# Connector.net
KiCad netlist of a schematic drawn in Altium Designer
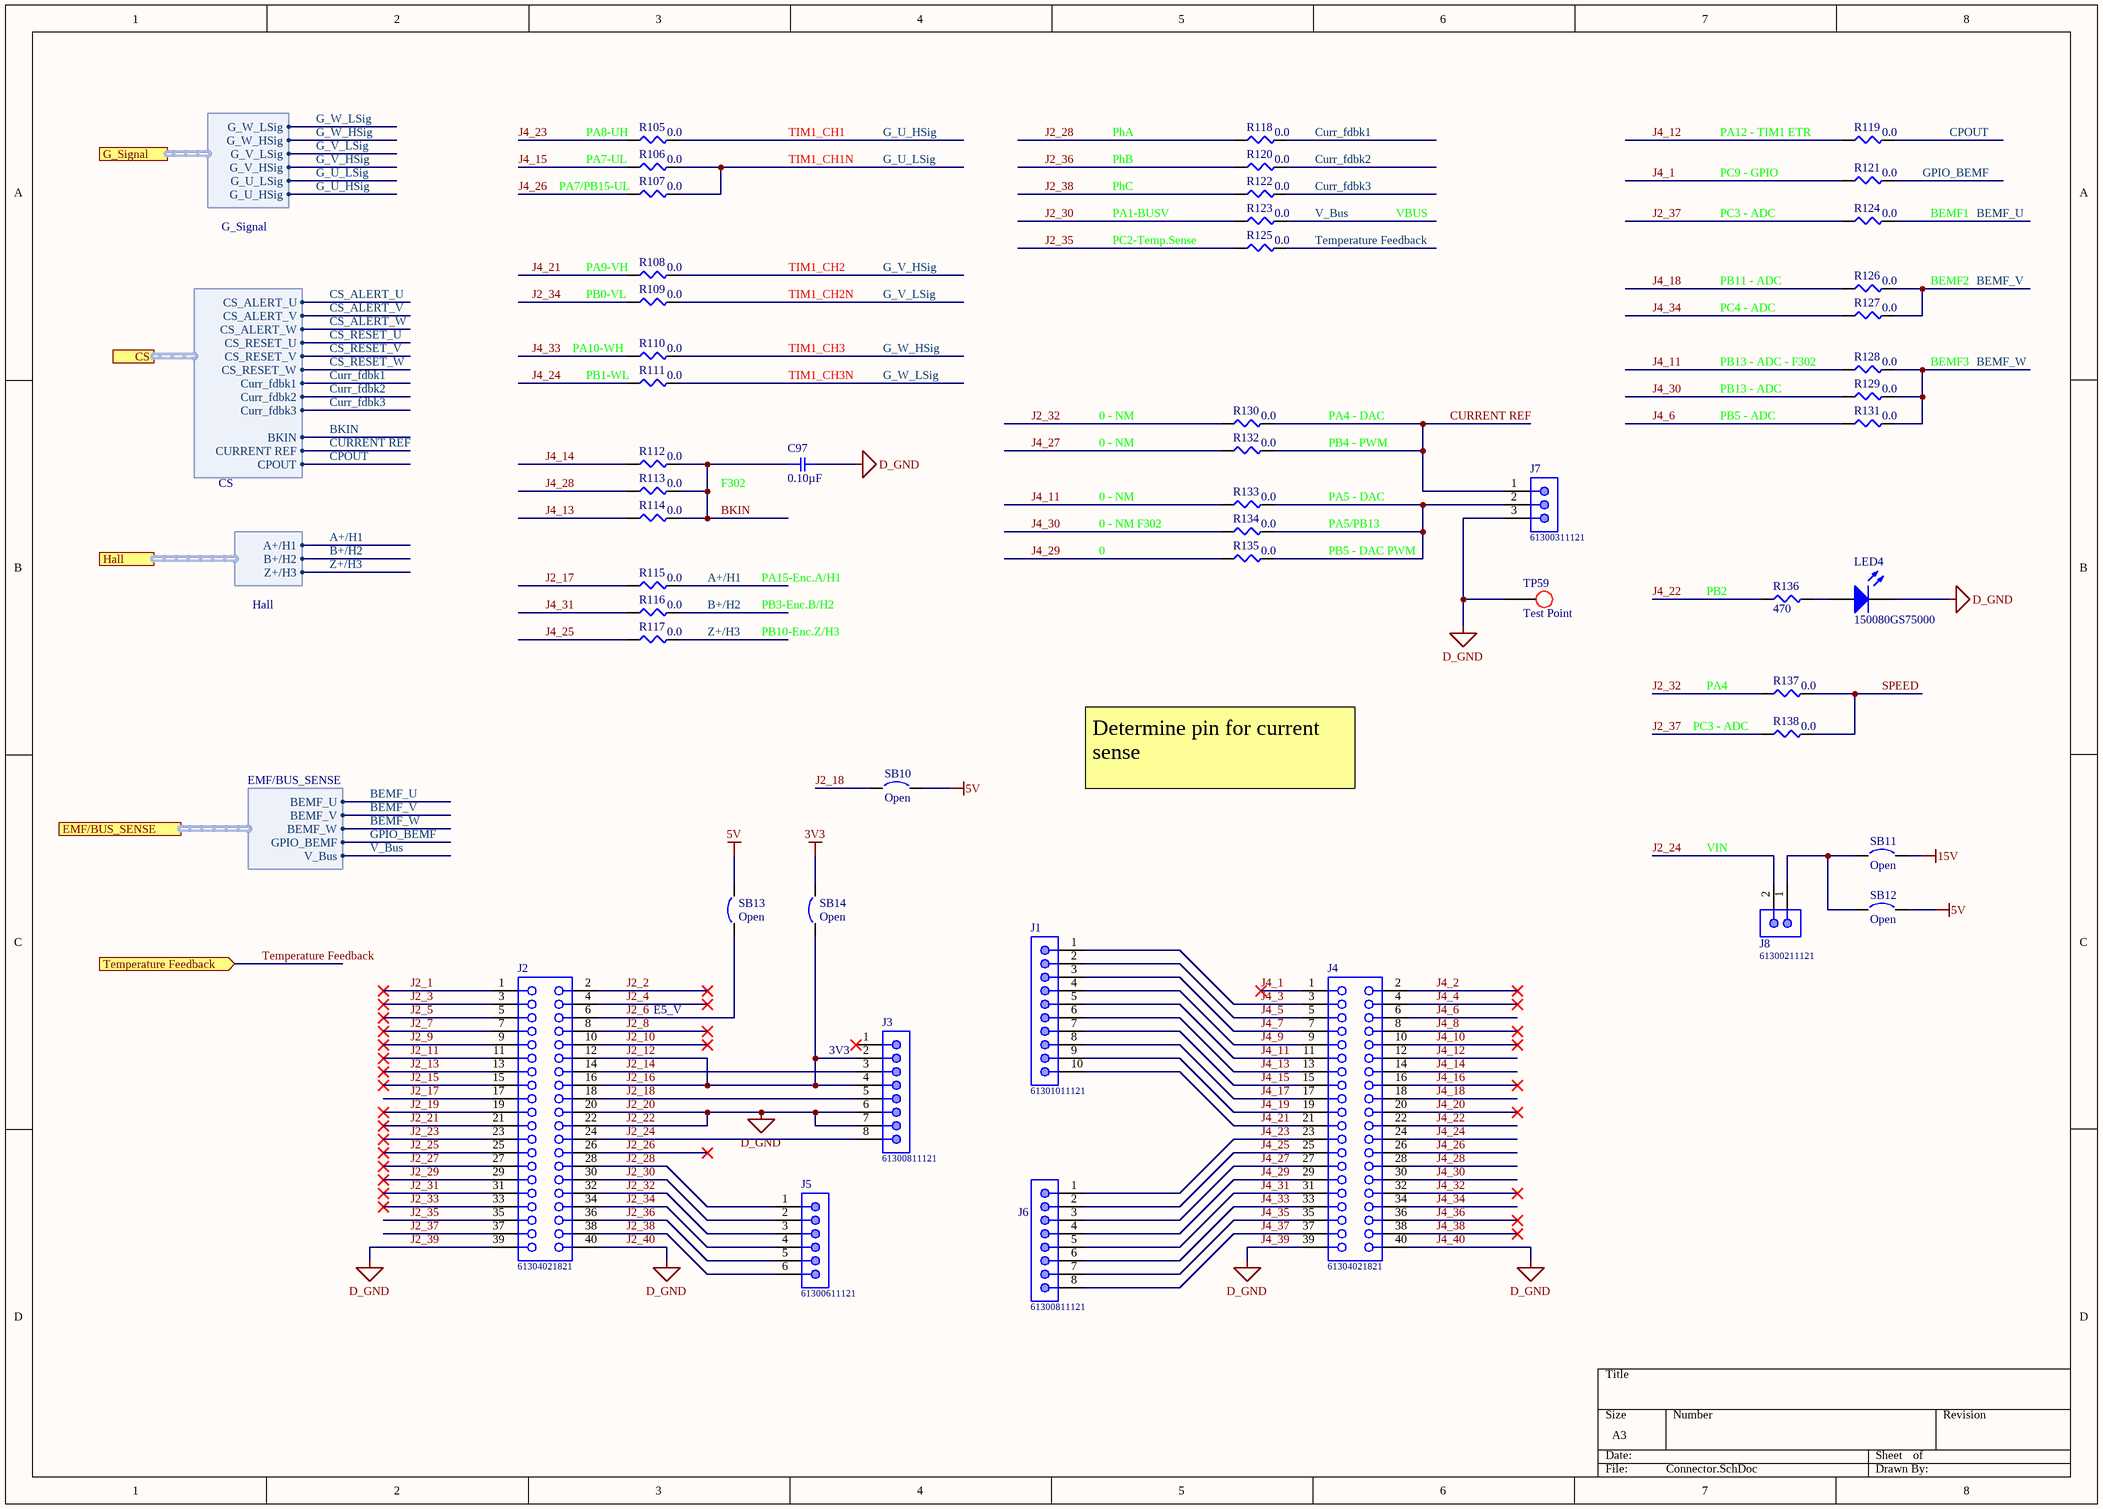
[diagram p0: Connector.SchDoc]

(export (version "E")
  (design (tool "Eeschema 10.0.6"))
  (components
    (comp (ref "C97")
      (value "0.10µF")
      (footprint "SMD-0805C")
      (description "CAP CER 0.1UF 50V X7R 0805")
      (fields
        (field (name "DIGI-KEY PART NUMBER") "490-11955-1-ND")
        (field (name "PART NUMBER") "GCD21BR71H104KA01L")
      )
      (libsource (lib "capacitor_murata_0805") (part "GCD21BR71H104KA01L"))
    )
    (comp (ref "J1")
      (value "61301011121")
      (footprint "61301011121")
      (description "WR-PHD Pin Header, THT, pitch 2.54mm, Single Row, Vertical, 10pin")
      (fields (field (name "PUBLISHER") "Wurth Elektronik"))
      (libsource (lib "o155175v243 Altium_WR-PHD (rev19a)") (part "61301011121"))
    )
    (comp (ref "J2")
      (value "61304021821")
      (footprint "61304021821")
      (description "WR-PHD Socket Header, THT, pitch 2.54mm, Dual Row, Vertical, 40pin")
      (fields (field (name "PUBLISHER") "Wurth Elektronik"))
      (libsource (lib "o155175v243 Altium_WR-PHD (rev19a)") (part "61304021821"))
    )
    (comp (ref "J3")
      (value "61300811121")
      (footprint "61300811121")
      (description "WR-PHD Pin Header, THT, pitch 2.54mm, Single Row, Vertical, 8pin")
      (fields (field (name "PUBLISHER") "Wurth Elektronik"))
      (libsource (lib "o155175v243 Altium_WR-PHD (rev19a)") (part "61300811121"))
    )
    (comp (ref "J4")
      (value "61304021821")
      (footprint "61304021821")
      (description "WR-PHD Socket Header, THT, pitch 2.54mm, Dual Row, Vertical, 40pin")
      (fields (field (name "PUBLISHER") "Wurth Elektronik"))
      (libsource (lib "o155175v243 Altium_WR-PHD (rev19a)") (part "61304021821"))
    )
    (comp (ref "J5")
      (value "61300611121")
      (footprint "61300611121")
      (description "WR-PHD Pin Header, THT, pitch 2.54mm, Single Row, Vertical, 6pin")
      (fields (field (name "PUBLISHER") "Wurth Elektronik"))
      (libsource (lib "o155175v243 Altium_WR-PHD (rev19a)") (part "61300611121"))
    )
    (comp (ref "J6")
      (value "61300811121")
      (footprint "61300811121")
      (description "WR-PHD Pin Header, THT, pitch 2.54mm, Single Row, Vertical, 8pin")
      (fields (field (name "PUBLISHER") "Wurth Elektronik"))
      (libsource (lib "o155175v243 Altium_WR-PHD (rev19a)") (part "61300811121"))
    )
    (comp (ref "J7")
      (value "61300311121")
      (footprint "61300311121")
      (description "WR-PHD Pin Header, THT, pitch 2.54mm, Single Row, Vertical, 3pin")
      (fields (field (name "PUBLISHER") "Wurth Elektronik"))
      (libsource (lib "o155175v243 Altium_WR-PHD (rev19a)") (part "61300311121"))
    )
    (comp (ref "J8")
      (value "61300211121")
      (footprint "61300211121")
      (description "WR-PHD Pin Header, THT, pitch 2.54mm, Single Row, Vertical, 2pin")
      (fields (field (name "PUBLISHER") "Wurth Elektronik"))
      (libsource (lib "o155175v243 Altium_WR-PHD (rev19a)") (part "61300211121"))
    )
    (comp (ref "LED4")
      (value "150080GS75000")
      (footprint "0805_A")
      (description "SMD mono-color Chip LED, WL-SMCW, Green")
      (libsource (lib "WL-SMCW SMD chip LED top view mono-color waterclear") (part "150080GS75000"))
    )
    (comp (ref "R105")
      (value "0.0")
      (footprint "SMD-0603-RES")
      (description "RES SMD 0.0OHM JUMPER 1/10W 0603")
      (fields (field (name "PART NUMBER") "ERJ-3GEY0R00V") (field (name "DIGI-KEY PART NUMBER") "P0.0GCT-ND"))
      (libsource (lib "Panasonic_ERJ_0603") (part "ERJ-3GEY0R00V"))
    )
    (comp (ref "R106")
      (value "0.0")
      (footprint "SMD-0603-RES")
      (description "RES SMD 0.0OHM JUMPER 1/10W 0603")
      (fields (field (name "PART NUMBER") "ERJ-3GEY0R00V") (field (name "DIGI-KEY PART NUMBER") "P0.0GCT-ND"))
      (libsource (lib "Panasonic_ERJ_0603") (part "ERJ-3GEY0R00V"))
    )
    (comp (ref "R107")
      (value "0.0")
      (footprint "SMD-0603-RES")
      (description "RES SMD 0.0OHM JUMPER 1/10W 0603")
      (fields (field (name "PART NUMBER") "ERJ-3GEY0R00V") (field (name "DIGI-KEY PART NUMBER") "P0.0GCT-ND"))
      (libsource (lib "Panasonic_ERJ_0603") (part "ERJ-3GEY0R00V"))
    )
    (comp (ref "R108")
      (value "0.0")
      (footprint "SMD-0603-RES")
      (description "RES SMD 0.0OHM JUMPER 1/10W 0603")
      (fields (field (name "PART NUMBER") "ERJ-3GEY0R00V") (field (name "DIGI-KEY PART NUMBER") "P0.0GCT-ND"))
      (libsource (lib "Panasonic_ERJ_0603") (part "ERJ-3GEY0R00V"))
    )
    (comp (ref "R109")
      (value "0.0")
      (footprint "SMD-0603-RES")
      (description "RES SMD 0.0OHM JUMPER 1/10W 0603")
      (fields (field (name "PART NUMBER") "ERJ-3GEY0R00V") (field (name "DIGI-KEY PART NUMBER") "P0.0GCT-ND"))
      (libsource (lib "Panasonic_ERJ_0603") (part "ERJ-3GEY0R00V"))
    )
    (comp (ref "R110")
      (value "0.0")
      (footprint "SMD-0603-RES")
      (description "RES SMD 0.0OHM JUMPER 1/10W 0603")
      (fields (field (name "PART NUMBER") "ERJ-3GEY0R00V") (field (name "DIGI-KEY PART NUMBER") "P0.0GCT-ND"))
      (libsource (lib "Panasonic_ERJ_0603") (part "ERJ-3GEY0R00V"))
    )
    (comp (ref "R111")
      (value "0.0")
      (footprint "SMD-0603-RES")
      (description "RES SMD 0.0OHM JUMPER 1/10W 0603")
      (fields (field (name "PART NUMBER") "ERJ-3GEY0R00V") (field (name "DIGI-KEY PART NUMBER") "P0.0GCT-ND"))
      (libsource (lib "Panasonic_ERJ_0603") (part "ERJ-3GEY0R00V"))
    )
    (comp (ref "R112")
      (value "0.0")
      (footprint "SMD-0603-RES")
      (description "RES SMD 0.0OHM JUMPER 1/10W 0603")
      (fields (field (name "PART NUMBER") "ERJ-3GEY0R00V") (field (name "DIGI-KEY PART NUMBER") "P0.0GCT-ND"))
      (libsource (lib "Panasonic_ERJ_0603") (part "ERJ-3GEY0R00V"))
    )
    (comp (ref "R113")
      (value "0.0")
      (footprint "SMD-0603-RES")
      (description "RES SMD 0.0OHM JUMPER 1/10W 0603")
      (fields (field (name "PART NUMBER") "ERJ-3GEY0R00V") (field (name "DIGI-KEY PART NUMBER") "P0.0GCT-ND"))
      (libsource (lib "Panasonic_ERJ_0603") (part "ERJ-3GEY0R00V"))
    )
    (comp (ref "R114")
      (value "0.0")
      (footprint "SMD-0603-RES")
      (description "RES SMD 0.0OHM JUMPER 1/10W 0603")
      (fields (field (name "PART NUMBER") "ERJ-3GEY0R00V") (field (name "DIGI-KEY PART NUMBER") "P0.0GCT-ND"))
      (libsource (lib "Panasonic_ERJ_0603") (part "ERJ-3GEY0R00V"))
    )
    (comp (ref "R115")
      (value "0.0")
      (footprint "SMD-0603-RES")
      (description "RES SMD 0.0OHM JUMPER 1/10W 0603")
      (fields (field (name "PART NUMBER") "ERJ-3GEY0R00V") (field (name "DIGI-KEY PART NUMBER") "P0.0GCT-ND"))
      (libsource (lib "Panasonic_ERJ_0603") (part "ERJ-3GEY0R00V"))
    )
    (comp (ref "R116")
      (value "0.0")
      (footprint "SMD-0603-RES")
      (description "RES SMD 0.0OHM JUMPER 1/10W 0603")
      (fields (field (name "PART NUMBER") "ERJ-3GEY0R00V") (field (name "DIGI-KEY PART NUMBER") "P0.0GCT-ND"))
      (libsource (lib "Panasonic_ERJ_0603") (part "ERJ-3GEY0R00V"))
    )
    (comp (ref "R117")
      (value "0.0")
      (footprint "SMD-0603-RES")
      (description "RES SMD 0.0OHM JUMPER 1/10W 0603")
      (fields (field (name "PART NUMBER") "ERJ-3GEY0R00V") (field (name "DIGI-KEY PART NUMBER") "P0.0GCT-ND"))
      (libsource (lib "Panasonic_ERJ_0603") (part "ERJ-3GEY0R00V"))
    )
    (comp (ref "R118")
      (value "0.0")
      (footprint "SMD-0603-RES")
      (description "RES SMD 0.0OHM JUMPER 1/10W 0603")
      (fields (field (name "PART NUMBER") "ERJ-3GEY0R00V") (field (name "DIGI-KEY PART NUMBER") "P0.0GCT-ND"))
      (libsource (lib "Panasonic_ERJ_0603") (part "ERJ-3GEY0R00V"))
    )
    (comp (ref "R119")
      (value "0.0")
      (footprint "SMD-0603-RES")
      (description "RES SMD 0.0OHM JUMPER 1/10W 0603")
      (fields (field (name "PART NUMBER") "ERJ-3GEY0R00V") (field (name "DIGI-KEY PART NUMBER") "P0.0GCT-ND"))
      (libsource (lib "Panasonic_ERJ_0603") (part "ERJ-3GEY0R00V"))
    )
    (comp (ref "R120")
      (value "0.0")
      (footprint "SMD-0603-RES")
      (description "RES SMD 0.0OHM JUMPER 1/10W 0603")
      (fields (field (name "PART NUMBER") "ERJ-3GEY0R00V") (field (name "DIGI-KEY PART NUMBER") "P0.0GCT-ND"))
      (libsource (lib "Panasonic_ERJ_0603") (part "ERJ-3GEY0R00V"))
    )
    (comp (ref "R121")
      (value "0.0")
      (footprint "SMD-0603-RES")
      (description "RES SMD 0.0OHM JUMPER 1/10W 0603")
      (fields (field (name "PART NUMBER") "ERJ-3GEY0R00V") (field (name "DIGI-KEY PART NUMBER") "P0.0GCT-ND"))
      (libsource (lib "Panasonic_ERJ_0603") (part "ERJ-3GEY0R00V"))
    )
    (comp (ref "R122")
      (value "0.0")
      (footprint "SMD-0603-RES")
      (description "RES SMD 0.0OHM JUMPER 1/10W 0603")
      (fields (field (name "PART NUMBER") "ERJ-3GEY0R00V") (field (name "DIGI-KEY PART NUMBER") "P0.0GCT-ND"))
      (libsource (lib "Panasonic_ERJ_0603") (part "ERJ-3GEY0R00V"))
    )
    (comp (ref "R123")
      (value "0.0")
      (footprint "SMD-0603-RES")
      (description "RES SMD 0.0OHM JUMPER 1/10W 0603")
      (fields (field (name "PART NUMBER") "ERJ-3GEY0R00V") (field (name "DIGI-KEY PART NUMBER") "P0.0GCT-ND"))
      (libsource (lib "Panasonic_ERJ_0603") (part "ERJ-3GEY0R00V"))
    )
    (comp (ref "R124")
      (value "0.0")
      (footprint "SMD-0603-RES")
      (description "RES SMD 0.0OHM JUMPER 1/10W 0603")
      (fields (field (name "PART NUMBER") "ERJ-3GEY0R00V") (field (name "DIGI-KEY PART NUMBER") "P0.0GCT-ND"))
      (libsource (lib "Panasonic_ERJ_0603") (part "ERJ-3GEY0R00V"))
    )
    (comp (ref "R125")
      (value "0.0")
      (footprint "SMD-0603-RES")
      (description "RES SMD 0.0OHM JUMPER 1/10W 0603")
      (fields (field (name "PART NUMBER") "ERJ-3GEY0R00V") (field (name "DIGI-KEY PART NUMBER") "P0.0GCT-ND"))
      (libsource (lib "Panasonic_ERJ_0603") (part "ERJ-3GEY0R00V"))
    )
    (comp (ref "R126")
      (value "0.0")
      (footprint "SMD-0603-RES")
      (description "RES SMD 0.0OHM JUMPER 1/10W 0603")
      (fields (field (name "PART NUMBER") "ERJ-3GEY0R00V") (field (name "DIGI-KEY PART NUMBER") "P0.0GCT-ND"))
      (libsource (lib "Panasonic_ERJ_0603") (part "ERJ-3GEY0R00V"))
    )
    (comp (ref "R127")
      (value "0.0")
      (footprint "SMD-0603-RES")
      (description "RES SMD 0.0OHM JUMPER 1/10W 0603")
      (fields (field (name "PART NUMBER") "ERJ-3GEY0R00V") (field (name "DIGI-KEY PART NUMBER") "P0.0GCT-ND"))
      (libsource (lib "Panasonic_ERJ_0603") (part "ERJ-3GEY0R00V"))
    )
    (comp (ref "R128")
      (value "0.0")
      (footprint "SMD-0603-RES")
      (description "RES SMD 0.0OHM JUMPER 1/10W 0603")
      (fields (field (name "PART NUMBER") "ERJ-3GEY0R00V") (field (name "DIGI-KEY PART NUMBER") "P0.0GCT-ND"))
      (libsource (lib "Panasonic_ERJ_0603") (part "ERJ-3GEY0R00V"))
    )
    (comp (ref "R129")
      (value "0.0")
      (footprint "SMD-0603-RES")
      (description "RES SMD 0.0OHM JUMPER 1/10W 0603")
      (fields (field (name "PART NUMBER") "ERJ-3GEY0R00V") (field (name "DIGI-KEY PART NUMBER") "P0.0GCT-ND"))
      (libsource (lib "Panasonic_ERJ_0603") (part "ERJ-3GEY0R00V"))
    )
    (comp (ref "R130")
      (value "0.0")
      (footprint "SMD-0603-RES")
      (description "RES SMD 0.0OHM JUMPER 1/10W 0603")
      (fields (field (name "PART NUMBER") "ERJ-3GEY0R00V") (field (name "DIGI-KEY PART NUMBER") "P0.0GCT-ND"))
      (libsource (lib "Panasonic_ERJ_0603") (part "ERJ-3GEY0R00V"))
    )
    (comp (ref "R131")
      (value "0.0")
      (footprint "SMD-0603-RES")
      (description "RES SMD 0.0OHM JUMPER 1/10W 0603")
      (fields (field (name "PART NUMBER") "ERJ-3GEY0R00V") (field (name "DIGI-KEY PART NUMBER") "P0.0GCT-ND"))
      (libsource (lib "Panasonic_ERJ_0603") (part "ERJ-3GEY0R00V"))
    )
    (comp (ref "R132")
      (value "0.0")
      (footprint "SMD-0603-RES")
      (description "RES SMD 0.0OHM JUMPER 1/10W 0603")
      (fields (field (name "PART NUMBER") "ERJ-3GEY0R00V") (field (name "DIGI-KEY PART NUMBER") "P0.0GCT-ND"))
      (libsource (lib "Panasonic_ERJ_0603") (part "ERJ-3GEY0R00V"))
    )
    (comp (ref "R133")
      (value "0.0")
      (footprint "SMD-0603-RES")
      (description "RES SMD 0.0OHM JUMPER 1/10W 0603")
      (fields (field (name "PART NUMBER") "ERJ-3GEY0R00V") (field (name "DIGI-KEY PART NUMBER") "P0.0GCT-ND"))
      (libsource (lib "Panasonic_ERJ_0603") (part "ERJ-3GEY0R00V"))
    )
    (comp (ref "R134")
      (value "0.0")
      (footprint "SMD-0603-RES")
      (description "RES SMD 0.0OHM JUMPER 1/10W 0603")
      (fields (field (name "PART NUMBER") "ERJ-3GEY0R00V") (field (name "DIGI-KEY PART NUMBER") "P0.0GCT-ND"))
      (libsource (lib "Panasonic_ERJ_0603") (part "ERJ-3GEY0R00V"))
    )
    (comp (ref "R135")
      (value "0.0")
      (footprint "SMD-0603-RES")
      (description "RES SMD 0.0OHM JUMPER 1/10W 0603")
      (fields (field (name "PART NUMBER") "ERJ-3GEY0R00V") (field (name "DIGI-KEY PART NUMBER") "P0.0GCT-ND"))
      (libsource (lib "Panasonic_ERJ_0603") (part "ERJ-3GEY0R00V"))
    )
    (comp (ref "R136")
      (value "470")
      (footprint "SMD-0603-RES")
      (description "RES SMD 470 OHM 1% 1/10W 0603")
      (fields (field (name "PART NUMBER") "ERJ-3EKF4700V") (field (name "DIGI-KEY PART NUMBER") "P470HCT-ND"))
      (libsource (lib "Panasonic_ERJ_0603") (part "ERJ-3EKF4700V"))
    )
    (comp (ref "R137")
      (value "0.0")
      (footprint "SMD-0603-RES")
      (description "RES SMD 0.0OHM JUMPER 1/10W 0603")
      (fields (field (name "PART NUMBER") "ERJ-3GEY0R00V") (field (name "DIGI-KEY PART NUMBER") "P0.0GCT-ND"))
      (libsource (lib "Panasonic_ERJ_0603") (part "ERJ-3GEY0R00V"))
    )
    (comp (ref "R138")
      (value "0.0")
      (footprint "SMD-0603-RES")
      (description "RES SMD 0.0OHM JUMPER 1/10W 0603")
      (fields (field (name "PART NUMBER") "ERJ-3GEY0R00V") (field (name "DIGI-KEY PART NUMBER") "P0.0GCT-ND"))
      (libsource (lib "Panasonic_ERJ_0603") (part "ERJ-3GEY0R00V"))
    )
    (comp (ref "SB10")
      (value "Open")
      (footprint "Solder Bridge - HP")
      (description "Circuit Breaker")
      (fields (field (name "PUBLISHER") "Altium Limited"))
      (libsource (lib "NUCLEOG431RB-Custom-IN-A2212") (part "Solder Bridge"))
    )
    (comp (ref "SB11")
      (value "Open")
      (footprint "Solder Bridge - HP")
      (description "Circuit Breaker")
      (fields (field (name "PUBLISHER") "Altium Limited"))
      (libsource (lib "NUCLEOG431RB-Custom-IN-A2212") (part "Solder Bridge"))
    )
    (comp (ref "SB12")
      (value "Open")
      (footprint "Solder Bridge - HP")
      (description "Circuit Breaker")
      (fields (field (name "PUBLISHER") "Altium Limited"))
      (libsource (lib "NUCLEOG431RB-Custom-IN-A2212") (part "Solder Bridge"))
    )
    (comp (ref "SB13")
      (value "Open")
      (footprint "Solder Bridge - HP")
      (description "Circuit Breaker")
      (fields (field (name "PUBLISHER") "Altium Limited"))
      (libsource (lib "NUCLEOG431RB-Custom-IN-A2212") (part "Solder Bridge"))
    )
    (comp (ref "SB14")
      (value "Open")
      (footprint "0805-Solder Bridge")
      (description "Circuit Breaker")
      (fields (field (name "PUBLISHER") "Altium Limited"))
      (libsource (lib "NUCLEOG431RB-Custom-IN-A2212") (part "Solder Bridge"))
    )
    (comp (ref "TP59")
      (value "Test Point")
      (footprint "Test_point_THT")
      (libsource (lib "NUCLEOG431RB-Custom-IN-A2212") (part "Test Point"))
    )
  )
  (nets
    (net (code "5") (name "/A+{slash}H1") (class "Default")
      (node (ref "R115") (pin "2") (pinfunction "2_2") (pintype "passive"))
    )
    (net (code "6") (name "/B+{slash}H2") (class "Default")
      (node (ref "R116") (pin "2") (pinfunction "2_2") (pintype "passive"))
    )
    (net (code "7") (name "/BEMF_U") (class "Default")
      (node (ref "R124") (pin "2") (pinfunction "2_2") (pintype "passive"))
    )
    (net (code "8") (name "/BEMF_V") (class "Default")
      (node (ref "R126") (pin "2") (pinfunction "2_2") (pintype "passive"))
      (node (ref "R127") (pin "2") (pinfunction "2_2") (pintype "passive"))
    )
    (net (code "9") (name "/BEMF_W") (class "Default")
      (node (ref "R128") (pin "2") (pinfunction "2_2") (pintype "passive"))
      (node (ref "R129") (pin "2") (pinfunction "2_2") (pintype "passive"))
      (node (ref "R131") (pin "2") (pinfunction "2_2") (pintype "passive"))
    )
    (net (code "10") (name "/BKIN") (class "Default")
      (node (ref "C97") (pin "1") (pinfunction "1_1") (pintype "passive"))
      (node (ref "R112") (pin "2") (pinfunction "2_2") (pintype "passive"))
      (node (ref "R113") (pin "2") (pinfunction "2_2") (pintype "passive"))
      (node (ref "R114") (pin "2") (pinfunction "2_2") (pintype "passive"))
    )
    (net (code "11") (name "/CPOUT") (class "Default")
      (node (ref "R119") (pin "2") (pinfunction "2_2") (pintype "passive"))
    )
    (net (code "18") (name "/CURRENT REF") (class "Default")
      (node (ref "J7") (pin "1") (pinfunction "1_1") (pintype "passive"))
      (node (ref "R130") (pin "2") (pinfunction "2_2") (pintype "passive"))
      (node (ref "R132") (pin "2") (pinfunction "2_2") (pintype "passive"))
    )
    (net (code "19") (name "/Curr_fdbk1") (class "Default")
      (node (ref "R118") (pin "2") (pinfunction "2_2") (pintype "passive"))
    )
    (net (code "20") (name "/Curr_fdbk2") (class "Default")
      (node (ref "R120") (pin "2") (pinfunction "2_2") (pintype "passive"))
    )
    (net (code "21") (name "/Curr_fdbk3") (class "Default")
      (node (ref "R122") (pin "2") (pinfunction "2_2") (pintype "passive"))
    )
    (net (code "22") (name "/GPIO_BEMF") (class "Default")
      (node (ref "R121") (pin "2") (pinfunction "2_2") (pintype "passive"))
    )
    (net (code "23") (name "/G_U_HSig") (class "Default")
      (node (ref "R105") (pin "2") (pinfunction "2_2") (pintype "passive"))
    )
    (net (code "24") (name "/G_U_LSig") (class "Default")
      (node (ref "R106") (pin "2") (pinfunction "2_2") (pintype "passive"))
      (node (ref "R107") (pin "2") (pinfunction "2_2") (pintype "passive"))
    )
    (net (code "25") (name "/G_V_HSig") (class "Default")
      (node (ref "R108") (pin "2") (pinfunction "2_2") (pintype "passive"))
    )
    (net (code "26") (name "/G_V_LSig") (class "Default")
      (node (ref "R109") (pin "2") (pinfunction "2_2") (pintype "passive"))
    )
    (net (code "27") (name "/G_W_HSig") (class "Default")
      (node (ref "R110") (pin "2") (pinfunction "2_2") (pintype "passive"))
    )
    (net (code "28") (name "/G_W_LSig") (class "Default")
      (node (ref "R111") (pin "2") (pinfunction "2_2") (pintype "passive"))
    )
    (net (code "29") (name "/J2_1") (class "Default")
      (node (ref "J2") (pin "1") (pinfunction "1_1") (pintype "passive+no_connect"))
    )
    (net (code "30") (name "/J2_2") (class "Default")
      (node (ref "J2") (pin "2") (pinfunction "2_2") (pintype "passive+no_connect"))
    )
    (net (code "31") (name "/J2_3") (class "Default")
      (node (ref "J2") (pin "3") (pinfunction "3_3") (pintype "passive+no_connect"))
    )
    (net (code "32") (name "/J2_4") (class "Default")
      (node (ref "J2") (pin "4") (pinfunction "4_4") (pintype "passive+no_connect"))
    )
    (net (code "33") (name "/J2_5") (class "Default")
      (node (ref "J2") (pin "5") (pinfunction "5_5") (pintype "passive+no_connect"))
    )
    (net (code "34") (name "/J2_6") (class "Default")
      (node (ref "J2") (pin "6") (pinfunction "6_6") (pintype "passive"))
      (node (ref "SB13") (pin "1") (pinfunction "1_1") (pintype "passive"))
    )
    (net (code "35") (name "/J2_7") (class "Default")
      (node (ref "J2") (pin "7") (pinfunction "7_7") (pintype "passive+no_connect"))
    )
    (net (code "36") (name "/J2_8") (class "Default")
      (node (ref "J2") (pin "8") (pinfunction "8_8") (pintype "passive+no_connect"))
    )
    (net (code "37") (name "/J2_9") (class "Default")
      (node (ref "J2") (pin "9") (pinfunction "9_9") (pintype "passive+no_connect"))
    )
    (net (code "38") (name "/J2_10") (class "Default")
      (node (ref "J2") (pin "10") (pinfunction "10_10") (pintype "passive+no_connect"))
    )
    (net (code "39") (name "/J2_11") (class "Default")
      (node (ref "J2") (pin "11") (pinfunction "11_11") (pintype "passive+no_connect"))
    )
    (net (code "40") (name "/J2_12") (class "Default")
      (node (ref "J2") (pin "12") (pinfunction "12_12") (pintype "passive"))
      (node (ref "J2") (pin "16") (pinfunction "16_16") (pintype "passive"))
      (node (ref "J3") (pin "2") (pinfunction "2_2") (pintype "passive"))
      (node (ref "J3") (pin "4") (pinfunction "4_4") (pintype "passive"))
      (node (ref "SB14") (pin "1") (pinfunction "1_1") (pintype "passive"))
    )
    (net (code "41") (name "/J2_13") (class "Default")
      (node (ref "J2") (pin "13") (pinfunction "13_13") (pintype "passive+no_connect"))
    )
    (net (code "42") (name "/J2_14") (class "Default")
      (node (ref "J2") (pin "14") (pinfunction "14_14") (pintype "passive"))
      (node (ref "J3") (pin "3") (pinfunction "3_3") (pintype "passive"))
    )
    (net (code "43") (name "/J2_15") (class "Default")
      (node (ref "J2") (pin "15") (pinfunction "15_15") (pintype "passive+no_connect"))
    )
    (net (code "44") (name "/J2_17") (class "Default")
      (node (ref "J2") (pin "17") (pinfunction "17_17") (pintype "passive"))
      (node (ref "R115") (pin "1") (pinfunction "1_1") (pintype "passive"))
    )
    (net (code "45") (name "/J2_18") (class "Default")
      (node (ref "J2") (pin "18") (pinfunction "18_18") (pintype "passive"))
      (node (ref "J3") (pin "5") (pinfunction "5_5") (pintype "passive"))
      (node (ref "SB10") (pin "1") (pinfunction "1_1") (pintype "passive"))
    )
    (net (code "46") (name "/J2_19") (class "Default")
      (node (ref "J2") (pin "19") (pinfunction "19_19") (pintype "passive+no_connect"))
    )
    (net (code "47") (name "/J2_21") (class "Default")
      (node (ref "J2") (pin "21") (pinfunction "21_21") (pintype "passive+no_connect"))
    )
    (net (code "48") (name "/J2_23") (class "Default")
      (node (ref "J2") (pin "23") (pinfunction "23_23") (pintype "passive+no_connect"))
    )
    (net (code "49") (name "/J2_24") (class "Default")
      (node (ref "J2") (pin "24") (pinfunction "24_24") (pintype "passive"))
      (node (ref "J3") (pin "8") (pinfunction "8_8") (pintype "passive"))
      (node (ref "J8") (pin "2") (pinfunction "2_2") (pintype "passive"))
    )
    (net (code "50") (name "/J2_25") (class "Default")
      (node (ref "J2") (pin "25") (pinfunction "25_25") (pintype "passive+no_connect"))
    )
    (net (code "51") (name "/J2_26") (class "Default")
      (node (ref "J2") (pin "26") (pinfunction "26_26") (pintype "passive+no_connect"))
    )
    (net (code "52") (name "/J2_27") (class "Default")
      (node (ref "J2") (pin "27") (pinfunction "27_27") (pintype "passive+no_connect"))
    )
    (net (code "53") (name "/J2_28") (class "Default")
      (node (ref "J2") (pin "28") (pinfunction "28_28") (pintype "passive"))
      (node (ref "J5") (pin "1") (pinfunction "1_1") (pintype "passive"))
      (node (ref "R118") (pin "1") (pinfunction "1_1") (pintype "passive"))
    )
    (net (code "54") (name "/J2_29") (class "Default")
      (node (ref "J2") (pin "29") (pinfunction "29_29") (pintype "passive+no_connect"))
    )
    (net (code "55") (name "/J2_30") (class "Default")
      (node (ref "J2") (pin "30") (pinfunction "30_30") (pintype "passive"))
      (node (ref "J5") (pin "2") (pinfunction "2_2") (pintype "passive"))
      (node (ref "R123") (pin "1") (pinfunction "1_1") (pintype "passive"))
    )
    (net (code "56") (name "/J2_31") (class "Default")
      (node (ref "J2") (pin "31") (pinfunction "31_31") (pintype "passive+no_connect"))
    )
    (net (code "57") (name "/J2_32") (class "Default")
      (node (ref "J2") (pin "32") (pinfunction "32_32") (pintype "passive"))
      (node (ref "J5") (pin "3") (pinfunction "3_3") (pintype "passive"))
      (node (ref "R130") (pin "1") (pinfunction "1_1") (pintype "passive"))
      (node (ref "R137") (pin "1") (pinfunction "1_1") (pintype "passive"))
    )
    (net (code "58") (name "/J2_33") (class "Default")
      (node (ref "J2") (pin "33") (pinfunction "33_33") (pintype "passive+no_connect"))
    )
    (net (code "59") (name "/J2_34") (class "Default")
      (node (ref "J2") (pin "34") (pinfunction "34_34") (pintype "passive"))
      (node (ref "J5") (pin "4") (pinfunction "4_4") (pintype "passive"))
      (node (ref "R109") (pin "1") (pinfunction "1_1") (pintype "passive"))
    )
    (net (code "60") (name "/J2_35") (class "Default")
      (node (ref "J2") (pin "35") (pinfunction "35_35") (pintype "passive"))
      (node (ref "R125") (pin "1") (pinfunction "1_1") (pintype "passive"))
    )
    (net (code "61") (name "/J2_36") (class "Default")
      (node (ref "J2") (pin "36") (pinfunction "36_36") (pintype "passive"))
      (node (ref "J5") (pin "5") (pinfunction "5_5") (pintype "passive"))
      (node (ref "R120") (pin "1") (pinfunction "1_1") (pintype "passive"))
    )
    (net (code "62") (name "/J2_37") (class "Default")
      (node (ref "J2") (pin "37") (pinfunction "37_37") (pintype "passive"))
      (node (ref "R124") (pin "1") (pinfunction "1_1") (pintype "passive"))
      (node (ref "R138") (pin "1") (pinfunction "1_1") (pintype "passive"))
    )
    (net (code "63") (name "/J2_38") (class "Default")
      (node (ref "J2") (pin "38") (pinfunction "38_38") (pintype "passive"))
      (node (ref "J5") (pin "6") (pinfunction "6_6") (pintype "passive"))
      (node (ref "R122") (pin "1") (pinfunction "1_1") (pintype "passive"))
    )
    (net (code "64") (name "/J4_1") (class "Default")
      (node (ref "J4") (pin "1") (pinfunction "1_1") (pintype "passive"))
      (node (ref "R121") (pin "1") (pinfunction "1_1") (pintype "passive"))
    )
    (net (code "65") (name "/J4_2") (class "Default")
      (node (ref "J4") (pin "2") (pinfunction "2_2") (pintype "passive+no_connect"))
    )
    (net (code "66") (name "/J4_3") (class "Default")
      (node (ref "J1") (pin "1") (pinfunction "1_1") (pintype "passive"))
      (node (ref "J4") (pin "3") (pinfunction "3_3") (pintype "passive"))
    )
    (net (code "67") (name "/J4_4") (class "Default")
      (node (ref "J4") (pin "4") (pinfunction "4_4") (pintype "passive+no_connect"))
    )
    (net (code "68") (name "/J4_5") (class "Default")
      (node (ref "J1") (pin "2") (pinfunction "2_2") (pintype "passive"))
      (node (ref "J4") (pin "5") (pinfunction "5_5") (pintype "passive"))
    )
    (net (code "69") (name "/J4_6") (class "Default")
      (node (ref "J4") (pin "6") (pinfunction "6_6") (pintype "passive"))
      (node (ref "R131") (pin "1") (pinfunction "1_1") (pintype "passive"))
    )
    (net (code "70") (name "/J4_7") (class "Default")
      (node (ref "J1") (pin "3") (pinfunction "3_3") (pintype "passive"))
      (node (ref "J4") (pin "7") (pinfunction "7_7") (pintype "passive"))
    )
    (net (code "71") (name "/J4_8") (class "Default")
      (node (ref "J4") (pin "8") (pinfunction "8_8") (pintype "passive+no_connect"))
    )
    (net (code "72") (name "/J4_9") (class "Default")
      (node (ref "J1") (pin "4") (pinfunction "4_4") (pintype "passive"))
      (node (ref "J4") (pin "9") (pinfunction "9_9") (pintype "passive"))
    )
    (net (code "73") (name "/J4_10") (class "Default")
      (node (ref "J4") (pin "10") (pinfunction "10_10") (pintype "passive+no_connect"))
    )
    (net (code "74") (name "/J4_11") (class "Default")
      (node (ref "J1") (pin "5") (pinfunction "5_5") (pintype "passive"))
      (node (ref "J4") (pin "11") (pinfunction "11_11") (pintype "passive"))
      (node (ref "R128") (pin "1") (pinfunction "1_1") (pintype "passive"))
      (node (ref "R133") (pin "1") (pinfunction "1_1") (pintype "passive"))
    )
    (net (code "75") (name "/J4_12") (class "Default")
      (node (ref "J4") (pin "12") (pinfunction "12_12") (pintype "passive"))
      (node (ref "R119") (pin "1") (pinfunction "1_1") (pintype "passive"))
    )
    (net (code "76") (name "/J4_13") (class "Default")
      (node (ref "J1") (pin "6") (pinfunction "6_6") (pintype "passive"))
      (node (ref "J4") (pin "13") (pinfunction "13_13") (pintype "passive"))
      (node (ref "R114") (pin "1") (pinfunction "1_1") (pintype "passive"))
    )
    (net (code "77") (name "/J4_14") (class "Default")
      (node (ref "J4") (pin "14") (pinfunction "14_14") (pintype "passive"))
      (node (ref "R112") (pin "1") (pinfunction "1_1") (pintype "passive"))
    )
    (net (code "78") (name "/J4_15") (class "Default")
      (node (ref "J1") (pin "7") (pinfunction "7_7") (pintype "passive"))
      (node (ref "J4") (pin "15") (pinfunction "15_15") (pintype "passive"))
      (node (ref "R106") (pin "1") (pinfunction "1_1") (pintype "passive"))
    )
    (net (code "79") (name "/J4_16") (class "Default")
      (node (ref "J4") (pin "16") (pinfunction "16_16") (pintype "passive+no_connect"))
    )
    (net (code "80") (name "/J4_17") (class "Default")
      (node (ref "J1") (pin "8") (pinfunction "8_8") (pintype "passive"))
      (node (ref "J4") (pin "17") (pinfunction "17_17") (pintype "passive"))
    )
    (net (code "81") (name "/J4_18") (class "Default")
      (node (ref "J4") (pin "18") (pinfunction "18_18") (pintype "passive"))
      (node (ref "R126") (pin "1") (pinfunction "1_1") (pintype "passive"))
    )
    (net (code "82") (name "/J4_19") (class "Default")
      (node (ref "J1") (pin "9") (pinfunction "9_9") (pintype "passive"))
      (node (ref "J4") (pin "19") (pinfunction "19_19") (pintype "passive"))
    )
    (net (code "83") (name "/J4_20") (class "Default")
      (node (ref "J4") (pin "20") (pinfunction "20_20") (pintype "passive+no_connect"))
    )
    (net (code "84") (name "/J4_21") (class "Default")
      (node (ref "J1") (pin "10") (pinfunction "10_10") (pintype "passive"))
      (node (ref "J4") (pin "21") (pinfunction "21_21") (pintype "passive"))
      (node (ref "R108") (pin "1") (pinfunction "1_1") (pintype "passive"))
    )
    (net (code "85") (name "/J4_22") (class "Default")
      (node (ref "J4") (pin "22") (pinfunction "22_22") (pintype "passive"))
      (node (ref "R136") (pin "1") (pinfunction "1_1") (pintype "passive"))
    )
    (net (code "86") (name "/J4_23") (class "Default")
      (node (ref "J4") (pin "23") (pinfunction "23_23") (pintype "passive"))
      (node (ref "J6") (pin "1") (pinfunction "1_1") (pintype "passive"))
      (node (ref "R105") (pin "1") (pinfunction "1_1") (pintype "passive"))
    )
    (net (code "87") (name "/J4_24") (class "Default")
      (node (ref "J4") (pin "24") (pinfunction "24_24") (pintype "passive"))
      (node (ref "R111") (pin "1") (pinfunction "1_1") (pintype "passive"))
    )
    (net (code "88") (name "/J4_25") (class "Default")
      (node (ref "J4") (pin "25") (pinfunction "25_25") (pintype "passive"))
      (node (ref "J6") (pin "2") (pinfunction "2_2") (pintype "passive"))
      (node (ref "R117") (pin "1") (pinfunction "1_1") (pintype "passive"))
    )
    (net (code "89") (name "/J4_26") (class "Default")
      (node (ref "J4") (pin "26") (pinfunction "26_26") (pintype "passive"))
      (node (ref "R107") (pin "1") (pinfunction "1_1") (pintype "passive"))
    )
    (net (code "90") (name "/J4_27") (class "Default")
      (node (ref "J4") (pin "27") (pinfunction "27_27") (pintype "passive"))
      (node (ref "J6") (pin "3") (pinfunction "3_3") (pintype "passive"))
      (node (ref "R132") (pin "1") (pinfunction "1_1") (pintype "passive"))
    )
    (net (code "91") (name "/J4_28") (class "Default")
      (node (ref "J4") (pin "28") (pinfunction "28_28") (pintype "passive"))
      (node (ref "R113") (pin "1") (pinfunction "1_1") (pintype "passive"))
    )
    (net (code "92") (name "/J4_29") (class "Default")
      (node (ref "J4") (pin "29") (pinfunction "29_29") (pintype "passive"))
      (node (ref "J6") (pin "4") (pinfunction "4_4") (pintype "passive"))
      (node (ref "R135") (pin "1") (pinfunction "1_1") (pintype "passive"))
    )
    (net (code "93") (name "/J4_30") (class "Default")
      (node (ref "J4") (pin "30") (pinfunction "30_30") (pintype "passive"))
      (node (ref "R129") (pin "1") (pinfunction "1_1") (pintype "passive"))
      (node (ref "R134") (pin "1") (pinfunction "1_1") (pintype "passive"))
    )
    (net (code "94") (name "/J4_31") (class "Default")
      (node (ref "J4") (pin "31") (pinfunction "31_31") (pintype "passive"))
      (node (ref "J6") (pin "5") (pinfunction "5_5") (pintype "passive"))
      (node (ref "R116") (pin "1") (pinfunction "1_1") (pintype "passive"))
    )
    (net (code "95") (name "/J4_32") (class "Default")
      (node (ref "J4") (pin "32") (pinfunction "32_32") (pintype "passive+no_connect"))
    )
    (net (code "96") (name "/J4_33") (class "Default")
      (node (ref "J4") (pin "33") (pinfunction "33_33") (pintype "passive"))
      (node (ref "J6") (pin "6") (pinfunction "6_6") (pintype "passive"))
      (node (ref "R110") (pin "1") (pinfunction "1_1") (pintype "passive"))
    )
    (net (code "97") (name "/J4_34") (class "Default")
      (node (ref "J4") (pin "34") (pinfunction "34_34") (pintype "passive"))
      (node (ref "R127") (pin "1") (pinfunction "1_1") (pintype "passive"))
    )
    (net (code "98") (name "/J4_35") (class "Default")
      (node (ref "J4") (pin "35") (pinfunction "35_35") (pintype "passive"))
      (node (ref "J6") (pin "7") (pinfunction "7_7") (pintype "passive"))
    )
    (net (code "99") (name "/J4_36") (class "Default")
      (node (ref "J4") (pin "36") (pinfunction "36_36") (pintype "passive+no_connect"))
    )
    (net (code "100") (name "/J4_37") (class "Default")
      (node (ref "J4") (pin "37") (pinfunction "37_37") (pintype "passive"))
      (node (ref "J6") (pin "8") (pinfunction "8_8") (pintype "passive"))
    )
    (net (code "101") (name "/J4_38") (class "Default")
      (node (ref "J4") (pin "38") (pinfunction "38_38") (pintype "passive+no_connect"))
    )
    (net (code "102") (name "/SPEED") (class "Default")
      (node (ref "R137") (pin "2") (pinfunction "2_2") (pintype "passive"))
      (node (ref "R138") (pin "2") (pinfunction "2_2") (pintype "passive"))
    )
    (net (code "103") (name "/Temperature Feedback") (class "Default")
      (node (ref "R125") (pin "2") (pinfunction "2_2") (pintype "passive"))
    )
    (net (code "104") (name "/V_Bus") (class "Default")
      (node (ref "R123") (pin "2") (pinfunction "2_2") (pintype "passive"))
    )
    (net (code "105") (name "/Z+{slash}H3") (class "Default")
      (node (ref "R117") (pin "2") (pinfunction "2_2") (pintype "passive"))
    )
    (net (code "110") (name "3V3") (class "Default")
      (node (ref "SB14") (pin "2") (pinfunction "2_2") (pintype "passive"))
    )
    (net (code "111") (name "5V") (class "Default")
      (node (ref "SB10") (pin "2") (pinfunction "2_2") (pintype "passive"))
      (node (ref "SB12") (pin "2") (pinfunction "2_2") (pintype "passive"))
      (node (ref "SB13") (pin "2") (pinfunction "2_2") (pintype "passive"))
    )
    (net (code "112") (name "15V") (class "Default")
      (node (ref "SB11") (pin "2") (pinfunction "2_2") (pintype "passive"))
    )
    (net (code "113") (name "D_GND") (class "Default")
      (node (ref "C97") (pin "2") (pinfunction "2_2") (pintype "passive"))
      (node (ref "J2") (pin "20") (pinfunction "20_20") (pintype "passive"))
      (node (ref "J2") (pin "22") (pinfunction "22_22") (pintype "passive"))
      (node (ref "J2") (pin "39") (pinfunction "39_39") (pintype "passive"))
      (node (ref "J2") (pin "40") (pinfunction "40_40") (pintype "passive"))
      (node (ref "J3") (pin "6") (pinfunction "6_6") (pintype "passive"))
      (node (ref "J3") (pin "7") (pinfunction "7_7") (pintype "passive"))
      (node (ref "J4") (pin "39") (pinfunction "39_39") (pintype "passive"))
      (node (ref "J4") (pin "40") (pinfunction "40_40") (pintype "passive"))
      (node (ref "J7") (pin "3") (pinfunction "3_3") (pintype "passive"))
      (node (ref "LED4") (pin "1") (pinfunction "K_1") (pintype "passive"))
      (node (ref "TP59") (pin "1") (pinfunction "1_1") (pintype "passive"))
    )
    (net (code "114") (name "Net-(J7-Pad2)") (class "Default")
      (node (ref "J7") (pin "2") (pinfunction "2_2") (pintype "passive"))
      (node (ref "R133") (pin "2") (pinfunction "2_2") (pintype "passive"))
      (node (ref "R134") (pin "2") (pinfunction "2_2") (pintype "passive"))
      (node (ref "R135") (pin "2") (pinfunction "2_2") (pintype "passive"))
    )
    (net (code "115") (name "Net-(J8-Pad1)") (class "Default")
      (node (ref "J8") (pin "1") (pinfunction "1_1") (pintype "passive"))
      (node (ref "SB11") (pin "1") (pinfunction "1_1") (pintype "passive"))
      (node (ref "SB12") (pin "1") (pinfunction "1_1") (pintype "passive"))
    )
    (net (code "116") (name "Net-(LED4-A)") (class "Default")
      (node (ref "LED4") (pin "2") (pinfunction "A_2") (pintype "passive"))
      (node (ref "R136") (pin "2") (pinfunction "2_2") (pintype "passive"))
    )
    (net (code "117") (name "unconnected-(J3-Pad1)") (class "Default")
      (node (ref "J3") (pin "1") (pinfunction "1_1") (pintype "passive+no_connect"))
    )
  )
)
